# PET_snes_gamepad.net
KiCad netlist of a schematic drawn in EAGLE
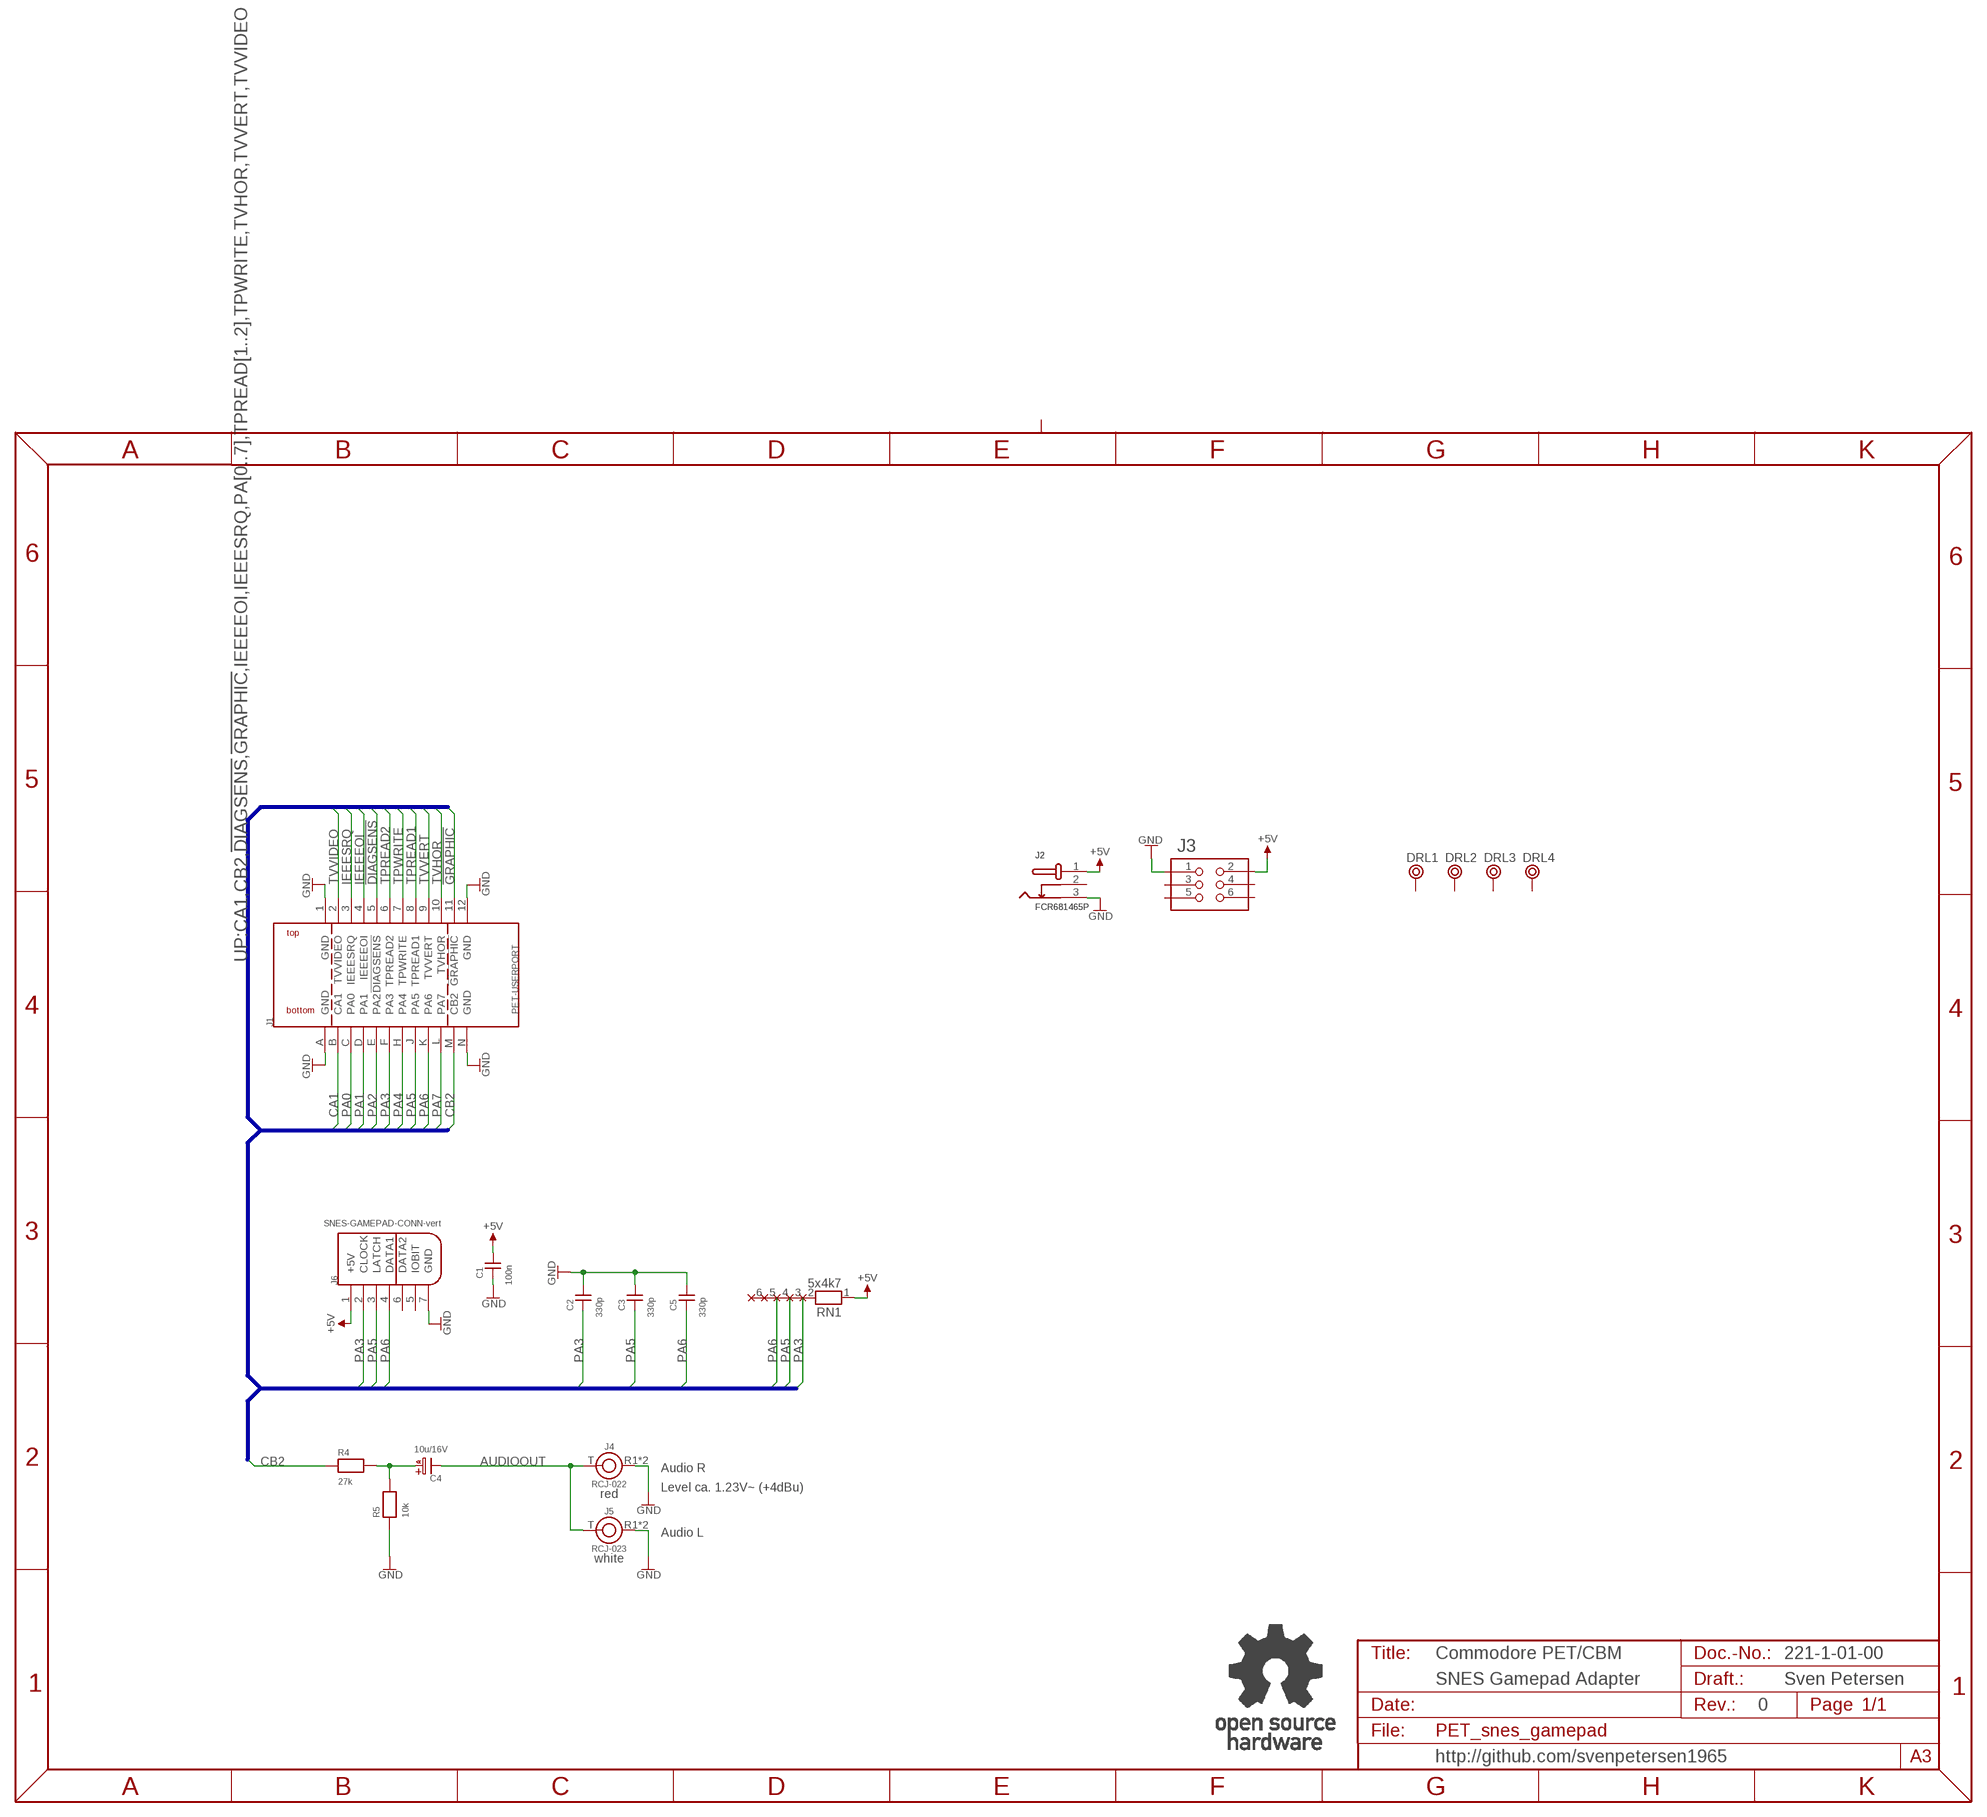
[diagram p0: schematic, sheet 1]

(export (version "E")
  (design (tool "Eeschema 10.0.6"))
  (components
    (comp (ref "C1")
      (value "100n")
      (footprint "eagle-import:C-2,5")
      (libsource (lib "eagle-import") (part "CAP01"))
    )
    (comp (ref "C2")
      (value "330p")
      (footprint "eagle-import:C-2,5")
      (libsource (lib "eagle-import") (part "CAP01"))
    )
    (comp (ref "C3")
      (value "330p")
      (footprint "eagle-import:C-2,5")
      (libsource (lib "eagle-import") (part "CAP01"))
    )
    (comp (ref "C4")
      (value "10u/16V")
      (footprint "eagle-import:C5,0_2,0")
      (libsource (lib "eagle-import") (part "C05,0/2,0"))
    )
    (comp (ref "C5")
      (value "330p")
      (footprint "eagle-import:C-2,5")
      (libsource (lib "eagle-import") (part "CAP01"))
    )
    (comp (ref "DRL1")
      (value "BOHR3,5")
      (footprint "eagle-import:BOHR3,5")
      (libsource (lib "eagle-import") (part "BOHR3,5"))
    )
    (comp (ref "DRL2")
      (value "BOHR3,5")
      (footprint "eagle-import:BOHR3,5")
      (libsource (lib "eagle-import") (part "BOHR3,5"))
    )
    (comp (ref "DRL3")
      (value "BOHR3,5")
      (footprint "eagle-import:BOHR3,5")
      (libsource (lib "eagle-import") (part "BOHR3,5"))
    )
    (comp (ref "DRL4")
      (value "BOHR3,5")
      (footprint "eagle-import:BOHR3,5")
      (libsource (lib "eagle-import") (part "BOHR3,5"))
    )
    (comp (ref "J1")
      (value "PET-USERPORT")
      (footprint "eagle-import:USERPORT")
      (libsource (lib "eagle-import") (part "PET-USERPORT"))
    )
    (comp (ref "J2")
      (value "FCR681465P")
      (footprint "eagle-import:FCR681465P")
      (libsource (lib "eagle-import") (part "FCR681465P"))
    )
    (comp (ref "J3")
      (value "2X03WV")
      (footprint "eagle-import:2X03WV")
      (libsource (lib "eagle-import") (part "2X03WV"))
    )
    (comp (ref "J4")
      (value "RCJ-022")
      (footprint "eagle-import:RCJ-02X")
      (libsource (lib "eagle-import") (part "RCJ-02X"))
    )
    (comp (ref "J5")
      (value "RCJ-023")
      (footprint "eagle-import:RCJ-02X")
      (libsource (lib "eagle-import") (part "RCJ-02X"))
    )
    (comp (ref "J6")
      (value "SNES-GAMEPAD-CONN-vert")
      (footprint "eagle-import:SNES_GAMEPAD_VERT")
      (libsource (lib "eagle-import") (part "GAMEPAD-CONN_SNESCONN"))
    )
    (comp (ref "R4")
      (value "27k")
      (footprint "eagle-import:R-10")
      (libsource (lib "eagle-import") (part "RES04"))
    )
    (comp (ref "R5")
      (value "10k")
      (footprint "eagle-import:R-10")
      (libsource (lib "eagle-import") (part "RES04"))
    )
    (comp (ref "RN1")
      (value "5x4k7")
      (footprint "eagle-import:RN-6")
      (libsource (lib "eagle-import") (part "RN05"))
    )
    (comp (ref "U$2")
      (value "OPEN_SOURCE_HW")
      (footprint "eagle-import:OPENHW")
      (libsource (lib "eagle-import") (part "OPEN_SOURCE_HW"))
    )
  )
  (nets
    (net (code "2") (name "+5V") (class "Default")
      (node (ref "C1") (pin "2") (pinfunction "2_2") (pintype "passive"))
      (node (ref "J2") (pin "1") (pinfunction "1_1") (pintype "bidirectional"))
      (node (ref "J3") (pin "2") (pinfunction "2_2") (pintype "passive"))
      (node (ref "J6") (pin "1") (pinfunction "+5V_1") (pintype "power_in"))
      (node (ref "RN1") (pin "1") (pinfunction "1_1") (pintype "passive"))
    )
    (net (code "3") (name "/AUDIOOUT") (class "Default")
      (node (ref "C4") (pin "K") (pinfunction "-_K") (pintype "passive"))
      (node (ref "J4") (pin "T") (pinfunction "T_T") (pintype "bidirectional"))
      (node (ref "J5") (pin "T") (pinfunction "T_T") (pintype "bidirectional"))
    )
    (net (code "4") (name "/CA1") (class "Default")
      (node (ref "J1") (pin "B") (pinfunction "CA1_B") (pintype "input"))
    )
    (net (code "5") (name "/CB2") (class "Default")
      (node (ref "J1") (pin "M") (pinfunction "CB2_M") (pintype "bidirectional"))
      (node (ref "R4") (pin "1") (pinfunction "1_1") (pintype "passive"))
    )
    (net (code "6") (name "/IEEEEOI") (class "Default")
      (node (ref "J1") (pin "4") (pinfunction "IEEEEOI_4") (pintype "output"))
    )
    (net (code "7") (name "/IEEESRQ") (class "Default")
      (node (ref "J1") (pin "3") (pinfunction "IEEESRQ_3") (pintype "output"))
    )
    (net (code "8") (name "/PA0") (class "Default")
      (node (ref "J1") (pin "C") (pinfunction "PA0_C") (pintype "bidirectional"))
    )
    (net (code "9") (name "/PA1") (class "Default")
      (node (ref "J1") (pin "D") (pinfunction "PA1_D") (pintype "bidirectional"))
    )
    (net (code "10") (name "/PA2") (class "Default")
      (node (ref "J1") (pin "E") (pinfunction "PA2_E") (pintype "bidirectional"))
    )
    (net (code "11") (name "/PA3") (class "Default")
      (node (ref "C2") (pin "1") (pinfunction "1_1") (pintype "passive"))
      (node (ref "J1") (pin "F") (pinfunction "PA3_F") (pintype "bidirectional"))
      (node (ref "J6") (pin "2") (pinfunction "CLOCK_2") (pintype "bidirectional"))
      (node (ref "RN1") (pin "2") (pinfunction "2_2") (pintype "passive"))
    )
    (net (code "12") (name "/PA4") (class "Default")
      (node (ref "J1") (pin "H") (pinfunction "PA4_H") (pintype "bidirectional"))
    )
    (net (code "13") (name "/PA5") (class "Default")
      (node (ref "C3") (pin "1") (pinfunction "1_1") (pintype "passive"))
      (node (ref "J1") (pin "J") (pinfunction "PA5_J") (pintype "bidirectional"))
      (node (ref "J6") (pin "3") (pinfunction "LATCH_3") (pintype "bidirectional"))
      (node (ref "RN1") (pin "3") (pinfunction "3_3") (pintype "passive"))
    )
    (net (code "14") (name "/PA6") (class "Default")
      (node (ref "C5") (pin "1") (pinfunction "1_1") (pintype "passive"))
      (node (ref "J1") (pin "K") (pinfunction "PA6_K") (pintype "bidirectional"))
      (node (ref "J6") (pin "4") (pinfunction "DATA1_4") (pintype "bidirectional"))
      (node (ref "RN1") (pin "4") (pinfunction "4_4") (pintype "passive"))
    )
    (net (code "15") (name "/PA7") (class "Default")
      (node (ref "J1") (pin "L") (pinfunction "PA7_L") (pintype "bidirectional"))
    )
    (net (code "16") (name "/TPREAD1") (class "Default")
      (node (ref "J1") (pin "8") (pinfunction "TPREAD1_8") (pintype "output"))
    )
    (net (code "17") (name "/TPREAD2") (class "Default")
      (node (ref "J1") (pin "6") (pinfunction "TPREAD2_6") (pintype "output"))
    )
    (net (code "18") (name "/TPWRITE") (class "Default")
      (node (ref "J1") (pin "7") (pinfunction "TPWRITE_7") (pintype "output"))
    )
    (net (code "19") (name "/TVHOR") (class "Default")
      (node (ref "J1") (pin "10") (pinfunction "TVHOR_10") (pintype "output"))
    )
    (net (code "20") (name "/TVVERT") (class "Default")
      (node (ref "J1") (pin "9") (pinfunction "TVVERT_9") (pintype "output"))
    )
    (net (code "21") (name "/TVVIDEO") (class "Default")
      (node (ref "J1") (pin "2") (pinfunction "TVVIDEO_2") (pintype "output"))
    )
    (net (code "23") (name "/~{DIAGSENS}") (class "Default")
      (node (ref "J1") (pin "5") (pinfunction "~{DIAGSENS}_5") (pintype "output"))
    )
    (net (code "24") (name "/~{GRAPHIC}") (class "Default")
      (node (ref "J1") (pin "11") (pinfunction "~{GRAPHIC}_11") (pintype "output"))
    )
    (net (code "25") (name "GND") (class "Default")
      (node (ref "C1") (pin "1") (pinfunction "1_1") (pintype "passive"))
      (node (ref "C2") (pin "2") (pinfunction "2_2") (pintype "passive"))
      (node (ref "C3") (pin "2") (pinfunction "2_2") (pintype "passive"))
      (node (ref "C5") (pin "2") (pinfunction "2_2") (pintype "passive"))
      (node (ref "J1") (pin "1") (pinfunction "GND_1") (pintype "power_in"))
      (node (ref "J1") (pin "12") (pinfunction "GND_12") (pintype "power_in"))
      (node (ref "J1") (pin "A") (pinfunction "GND_A") (pintype "power_in"))
      (node (ref "J1") (pin "N") (pinfunction "GND_N") (pintype "power_in"))
      (node (ref "J2") (pin "3") (pinfunction "3_3") (pintype "bidirectional"))
      (node (ref "J3") (pin "1") (pinfunction "1_1") (pintype "passive"))
      (node (ref "J4") (pin "R1") (pinfunction "R_R1") (pintype "bidirectional"))
      (node (ref "J4") (pin "R2") (pinfunction "R_R2") (pintype "bidirectional"))
      (node (ref "J5") (pin "R1") (pinfunction "R_R1") (pintype "bidirectional"))
      (node (ref "J5") (pin "R2") (pinfunction "R_R2") (pintype "bidirectional"))
      (node (ref "J6") (pin "7") (pinfunction "GND_7") (pintype "power_in"))
      (node (ref "R5") (pin "1") (pinfunction "1_1") (pintype "passive"))
    )
    (net (code "26") (name "Net-(C4-+)") (class "Default")
      (node (ref "C4") (pin "A") (pinfunction "+_A") (pintype "passive"))
      (node (ref "R4") (pin "2") (pinfunction "2_2") (pintype "passive"))
      (node (ref "R5") (pin "2") (pinfunction "2_2") (pintype "passive"))
    )
    (net (code "27") (name "unconnected-(DRL1-PadP$1)") (class "Default")
      (node (ref "DRL1") (pin "P$1") (pinfunction "P$1_P$1") (pintype "passive"))
    )
    (net (code "28") (name "unconnected-(DRL2-PadP$1)") (class "Default")
      (node (ref "DRL2") (pin "P$1") (pinfunction "P$1_P$1") (pintype "passive"))
    )
    (net (code "29") (name "unconnected-(DRL3-PadP$1)") (class "Default")
      (node (ref "DRL3") (pin "P$1") (pinfunction "P$1_P$1") (pintype "passive"))
    )
    (net (code "30") (name "unconnected-(DRL4-PadP$1)") (class "Default")
      (node (ref "DRL4") (pin "P$1") (pinfunction "P$1_P$1") (pintype "passive"))
    )
    (net (code "31") (name "unconnected-(J2-Pad2)") (class "Default")
      (node (ref "J2") (pin "2") (pinfunction "2_2") (pintype "bidirectional"))
    )
    (net (code "32") (name "unconnected-(J3-Pad3)") (class "Default")
      (node (ref "J3") (pin "3") (pinfunction "3_3") (pintype "passive"))
    )
    (net (code "33") (name "unconnected-(J3-Pad4)") (class "Default")
      (node (ref "J3") (pin "4") (pinfunction "4_4") (pintype "passive"))
    )
    (net (code "34") (name "unconnected-(J3-Pad5)") (class "Default")
      (node (ref "J3") (pin "5") (pinfunction "5_5") (pintype "passive"))
    )
    (net (code "35") (name "unconnected-(J3-Pad6)") (class "Default")
      (node (ref "J3") (pin "6") (pinfunction "6_6") (pintype "passive"))
    )
    (net (code "36") (name "unconnected-(J6-DATA2-Pad6)") (class "Default")
      (node (ref "J6") (pin "6") (pinfunction "DATA2_6") (pintype "bidirectional"))
    )
    (net (code "37") (name "unconnected-(J6-IOBIT-Pad5)") (class "Default")
      (node (ref "J6") (pin "5") (pinfunction "IOBIT_5") (pintype "bidirectional"))
    )
    (net (code "38") (name "unconnected-(RN1-Pad5)") (class "Default")
      (node (ref "RN1") (pin "5") (pinfunction "5_5") (pintype "passive"))
    )
    (net (code "39") (name "unconnected-(RN1-Pad6)") (class "Default")
      (node (ref "RN1") (pin "6") (pinfunction "6_6") (pintype "passive"))
    )
  )
)
